# 8-Bit_Selector_2-to-1.net
KiCad netlist of a schematic drawn in EAGLE
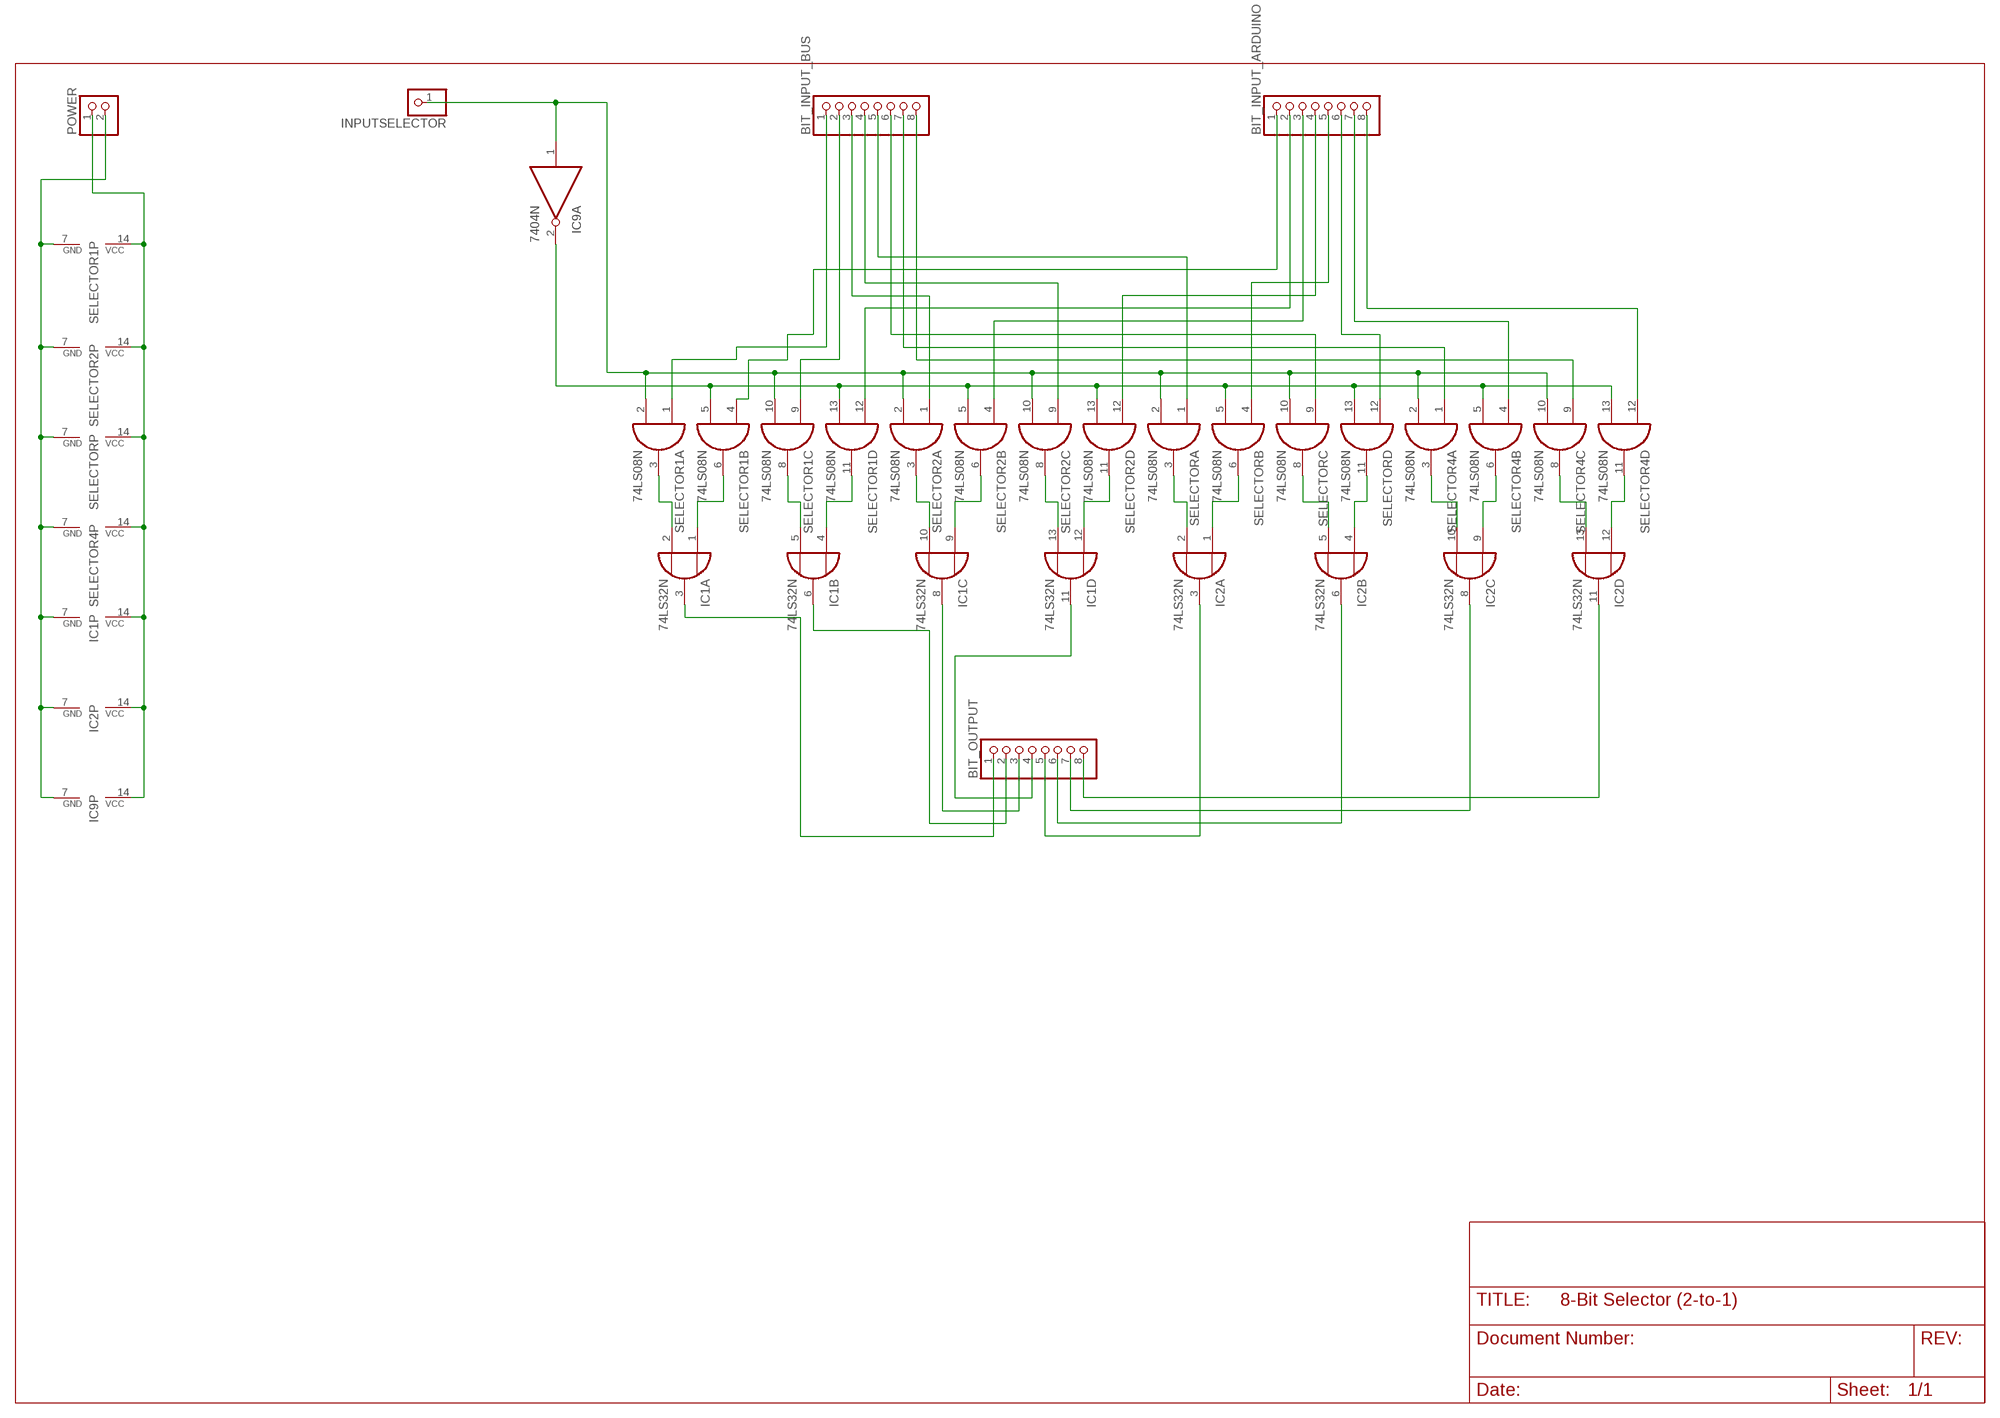
[diagram p0: schematic, sheet 1]

(export (version "E")
  (design (tool "Eeschema 10.0.6"))
  (components
    (comp (ref "BIT_INPUT_ARDUINO")
      (value "PINHD-1X8")
      (footprint "eagle-import:1X08")
      (libsource (lib "eagle-import") (part "PINHD-1X8"))
    )
    (comp (ref "BIT_INPUT_BUS")
      (value "PINHD-1X8")
      (footprint "eagle-import:1X08")
      (libsource (lib "eagle-import") (part "PINHD-1X8"))
    )
    (comp (ref "BIT_OUTPUT")
      (value "PINHD-1X8")
      (footprint "eagle-import:1X08")
      (libsource (lib "eagle-import") (part "PINHD-1X8"))
    )
    (comp (ref "IC1")
      (value "74LS32N")
      (footprint "eagle-import:DIL14")
      (libsource (lib "eagle-import") (part "7432NLS"))
    )
    (comp (ref "IC2")
      (value "74LS32N")
      (footprint "eagle-import:DIL14")
      (libsource (lib "eagle-import") (part "7432NLS"))
    )
    (comp (ref "IC9")
      (value "7404N")
      (footprint "eagle-import:DIL14")
      (libsource (lib "eagle-import") (part "7404N"))
    )
    (comp (ref "INPUTSELECTOR")
      (value "PINHD-1X1")
      (footprint "eagle-import:1X01")
      (libsource (lib "eagle-import") (part "PINHD-1X1"))
    )
    (comp (ref "POWER")
      (value "PINHD-1X2")
      (footprint "eagle-import:1X02")
      (libsource (lib "eagle-import") (part "PINHD-1X2"))
    )
    (comp (ref "SELECTOR")
      (value "74LS08N")
      (footprint "eagle-import:DIL14")
      (libsource (lib "eagle-import") (part "7408NLS"))
    )
    (comp (ref "SELECTOR1")
      (value "74LS08N")
      (footprint "eagle-import:DIL14")
      (libsource (lib "eagle-import") (part "7408NLS"))
    )
    (comp (ref "SELECTOR2")
      (value "74LS08N")
      (footprint "eagle-import:DIL14")
      (libsource (lib "eagle-import") (part "7408NLS"))
    )
    (comp (ref "SELECTOR4")
      (value "74LS08N")
      (footprint "eagle-import:DIL14")
      (libsource (lib "eagle-import") (part "7408NLS"))
    )
  )
  (nets
    (net (code "1") (name "Net-(IC1A-I0)") (class "Default")
      (node (ref "IC1") (pin "1") (pinfunction "I0_1") (pintype "input"))
      (node (ref "SELECTOR1") (pin "6") (pinfunction "O_6") (pintype "output"))
    )
    (net (code "2") (name "Net-(IC1A-I1)") (class "Default")
      (node (ref "IC1") (pin "2") (pinfunction "I1_2") (pintype "input"))
      (node (ref "SELECTOR1") (pin "3") (pinfunction "O_3") (pintype "output"))
    )
    (net (code "3") (name "Net-(IC1A-O)") (class "Default")
      (node (ref "BIT_OUTPUT") (pin "1") (pinfunction "1_1") (pintype "passive"))
      (node (ref "IC1") (pin "3") (pinfunction "O_3") (pintype "output"))
    )
    (net (code "4") (name "Net-(IC1B-I0)") (class "Default")
      (node (ref "IC1") (pin "4") (pinfunction "I0_4") (pintype "input"))
      (node (ref "SELECTOR1") (pin "11") (pinfunction "O_11") (pintype "output"))
    )
    (net (code "5") (name "Net-(IC1B-I1)") (class "Default")
      (node (ref "IC1") (pin "5") (pinfunction "I1_5") (pintype "input"))
      (node (ref "SELECTOR1") (pin "8") (pinfunction "O_8") (pintype "output"))
    )
    (net (code "6") (name "Net-(IC1B-O)") (class "Default")
      (node (ref "BIT_OUTPUT") (pin "2") (pinfunction "2_2") (pintype "passive"))
      (node (ref "IC1") (pin "6") (pinfunction "O_6") (pintype "output"))
    )
    (net (code "7") (name "Net-(IC1C-I0)") (class "Default")
      (node (ref "IC1") (pin "9") (pinfunction "I0_9") (pintype "input"))
      (node (ref "SELECTOR2") (pin "6") (pinfunction "O_6") (pintype "output"))
    )
    (net (code "8") (name "Net-(IC1C-I1)") (class "Default")
      (node (ref "IC1") (pin "10") (pinfunction "I1_10") (pintype "input"))
      (node (ref "SELECTOR2") (pin "3") (pinfunction "O_3") (pintype "output"))
    )
    (net (code "9") (name "Net-(IC1C-O)") (class "Default")
      (node (ref "BIT_OUTPUT") (pin "3") (pinfunction "3_3") (pintype "passive"))
      (node (ref "IC1") (pin "8") (pinfunction "O_8") (pintype "output"))
    )
    (net (code "10") (name "Net-(IC1D-I0)") (class "Default")
      (node (ref "IC1") (pin "12") (pinfunction "I0_12") (pintype "input"))
      (node (ref "SELECTOR2") (pin "11") (pinfunction "O_11") (pintype "output"))
    )
    (net (code "11") (name "Net-(IC1D-I1)") (class "Default")
      (node (ref "IC1") (pin "13") (pinfunction "I1_13") (pintype "input"))
      (node (ref "SELECTOR2") (pin "8") (pinfunction "O_8") (pintype "output"))
    )
    (net (code "12") (name "Net-(IC1D-O)") (class "Default")
      (node (ref "BIT_OUTPUT") (pin "4") (pinfunction "4_4") (pintype "passive"))
      (node (ref "IC1") (pin "11") (pinfunction "O_11") (pintype "output"))
    )
    (net (code "13") (name "Net-(IC1E-GND)") (class "Default")
      (node (ref "IC1") (pin "7") (pinfunction "GND_7") (pintype "power_in"))
      (node (ref "IC2") (pin "7") (pinfunction "GND_7") (pintype "power_in"))
      (node (ref "IC9") (pin "7") (pinfunction "GND_7") (pintype "power_in"))
      (node (ref "POWER") (pin "2") (pinfunction "2_2") (pintype "passive"))
      (node (ref "SELECTOR") (pin "7") (pinfunction "GND_7") (pintype "power_in"))
      (node (ref "SELECTOR1") (pin "7") (pinfunction "GND_7") (pintype "power_in"))
      (node (ref "SELECTOR2") (pin "7") (pinfunction "GND_7") (pintype "power_in"))
      (node (ref "SELECTOR4") (pin "7") (pinfunction "GND_7") (pintype "power_in"))
    )
    (net (code "14") (name "Net-(IC1E-VCC)") (class "Default")
      (node (ref "IC1") (pin "14") (pinfunction "VCC_14") (pintype "power_in"))
      (node (ref "IC2") (pin "14") (pinfunction "VCC_14") (pintype "power_in"))
      (node (ref "IC9") (pin "14") (pinfunction "VCC_14") (pintype "power_in"))
      (node (ref "POWER") (pin "1") (pinfunction "1_1") (pintype "passive"))
      (node (ref "SELECTOR") (pin "14") (pinfunction "VCC_14") (pintype "power_in"))
      (node (ref "SELECTOR1") (pin "14") (pinfunction "VCC_14") (pintype "power_in"))
      (node (ref "SELECTOR2") (pin "14") (pinfunction "VCC_14") (pintype "power_in"))
      (node (ref "SELECTOR4") (pin "14") (pinfunction "VCC_14") (pintype "power_in"))
    )
    (net (code "15") (name "Net-(IC2A-I0)") (class "Default")
      (node (ref "IC2") (pin "1") (pinfunction "I0_1") (pintype "input"))
      (node (ref "SELECTOR") (pin "6") (pinfunction "O_6") (pintype "output"))
    )
    (net (code "16") (name "Net-(IC2A-I1)") (class "Default")
      (node (ref "IC2") (pin "2") (pinfunction "I1_2") (pintype "input"))
      (node (ref "SELECTOR") (pin "3") (pinfunction "O_3") (pintype "output"))
    )
    (net (code "17") (name "Net-(IC2A-O)") (class "Default")
      (node (ref "BIT_OUTPUT") (pin "5") (pinfunction "5_5") (pintype "passive"))
      (node (ref "IC2") (pin "3") (pinfunction "O_3") (pintype "output"))
    )
    (net (code "18") (name "Net-(IC2B-I0)") (class "Default")
      (node (ref "IC2") (pin "4") (pinfunction "I0_4") (pintype "input"))
      (node (ref "SELECTOR") (pin "11") (pinfunction "O_11") (pintype "output"))
    )
    (net (code "19") (name "Net-(IC2B-I1)") (class "Default")
      (node (ref "IC2") (pin "5") (pinfunction "I1_5") (pintype "input"))
      (node (ref "SELECTOR") (pin "8") (pinfunction "O_8") (pintype "output"))
    )
    (net (code "20") (name "Net-(IC2B-O)") (class "Default")
      (node (ref "BIT_OUTPUT") (pin "6") (pinfunction "6_6") (pintype "passive"))
      (node (ref "IC2") (pin "6") (pinfunction "O_6") (pintype "output"))
    )
    (net (code "21") (name "Net-(IC2C-I0)") (class "Default")
      (node (ref "IC2") (pin "9") (pinfunction "I0_9") (pintype "input"))
      (node (ref "SELECTOR4") (pin "6") (pinfunction "O_6") (pintype "output"))
    )
    (net (code "22") (name "Net-(IC2C-I1)") (class "Default")
      (node (ref "IC2") (pin "10") (pinfunction "I1_10") (pintype "input"))
      (node (ref "SELECTOR4") (pin "3") (pinfunction "O_3") (pintype "output"))
    )
    (net (code "23") (name "Net-(IC2C-O)") (class "Default")
      (node (ref "BIT_OUTPUT") (pin "7") (pinfunction "7_7") (pintype "passive"))
      (node (ref "IC2") (pin "8") (pinfunction "O_8") (pintype "output"))
    )
    (net (code "24") (name "Net-(IC2D-I0)") (class "Default")
      (node (ref "IC2") (pin "12") (pinfunction "I0_12") (pintype "input"))
      (node (ref "SELECTOR4") (pin "11") (pinfunction "O_11") (pintype "output"))
    )
    (net (code "25") (name "Net-(IC2D-I1)") (class "Default")
      (node (ref "IC2") (pin "13") (pinfunction "I1_13") (pintype "input"))
      (node (ref "SELECTOR4") (pin "8") (pinfunction "O_8") (pintype "output"))
    )
    (net (code "26") (name "Net-(IC2D-O)") (class "Default")
      (node (ref "BIT_OUTPUT") (pin "8") (pinfunction "8_8") (pintype "passive"))
      (node (ref "IC2") (pin "11") (pinfunction "O_11") (pintype "output"))
    )
    (net (code "27") (name "Net-(IC9A-I)") (class "Default")
      (node (ref "IC9") (pin "1") (pinfunction "I_1") (pintype "input"))
      (node (ref "INPUTSELECTOR") (pin "1") (pinfunction "1_1") (pintype "passive"))
      (node (ref "SELECTOR") (pin "10") (pinfunction "I1_10") (pintype "input"))
      (node (ref "SELECTOR") (pin "2") (pinfunction "I1_2") (pintype "input"))
      (node (ref "SELECTOR1") (pin "10") (pinfunction "I1_10") (pintype "input"))
      (node (ref "SELECTOR1") (pin "2") (pinfunction "I1_2") (pintype "input"))
      (node (ref "SELECTOR2") (pin "10") (pinfunction "I1_10") (pintype "input"))
      (node (ref "SELECTOR2") (pin "2") (pinfunction "I1_2") (pintype "input"))
      (node (ref "SELECTOR4") (pin "10") (pinfunction "I1_10") (pintype "input"))
      (node (ref "SELECTOR4") (pin "2") (pinfunction "I1_2") (pintype "input"))
    )
    (net (code "28") (name "Net-(IC9A-O)") (class "Default")
      (node (ref "IC9") (pin "2") (pinfunction "O_2") (pintype "output"))
      (node (ref "SELECTOR") (pin "13") (pinfunction "I1_13") (pintype "input"))
      (node (ref "SELECTOR") (pin "5") (pinfunction "I1_5") (pintype "input"))
      (node (ref "SELECTOR1") (pin "13") (pinfunction "I1_13") (pintype "input"))
      (node (ref "SELECTOR1") (pin "5") (pinfunction "I1_5") (pintype "input"))
      (node (ref "SELECTOR2") (pin "13") (pinfunction "I1_13") (pintype "input"))
      (node (ref "SELECTOR2") (pin "5") (pinfunction "I1_5") (pintype "input"))
      (node (ref "SELECTOR4") (pin "13") (pinfunction "I1_13") (pintype "input"))
      (node (ref "SELECTOR4") (pin "5") (pinfunction "I1_5") (pintype "input"))
    )
    (net (code "29") (name "Net-(SELECTOR1A-I0)") (class "Default")
      (node (ref "BIT_INPUT_BUS") (pin "1") (pinfunction "1_1") (pintype "passive"))
      (node (ref "SELECTOR1") (pin "1") (pinfunction "I0_1") (pintype "input"))
    )
    (net (code "30") (name "Net-(SELECTOR1B-I0)") (class "Default")
      (node (ref "BIT_INPUT_ARDUINO") (pin "1") (pinfunction "1_1") (pintype "passive"))
      (node (ref "SELECTOR1") (pin "4") (pinfunction "I0_4") (pintype "input"))
    )
    (net (code "31") (name "Net-(SELECTOR1C-I0)") (class "Default")
      (node (ref "BIT_INPUT_BUS") (pin "2") (pinfunction "2_2") (pintype "passive"))
      (node (ref "SELECTOR1") (pin "9") (pinfunction "I0_9") (pintype "input"))
    )
    (net (code "32") (name "Net-(SELECTOR1D-I0)") (class "Default")
      (node (ref "BIT_INPUT_ARDUINO") (pin "2") (pinfunction "2_2") (pintype "passive"))
      (node (ref "SELECTOR1") (pin "12") (pinfunction "I0_12") (pintype "input"))
    )
    (net (code "33") (name "Net-(SELECTOR2A-I0)") (class "Default")
      (node (ref "BIT_INPUT_BUS") (pin "3") (pinfunction "3_3") (pintype "passive"))
      (node (ref "SELECTOR2") (pin "1") (pinfunction "I0_1") (pintype "input"))
    )
    (net (code "34") (name "Net-(SELECTOR2B-I0)") (class "Default")
      (node (ref "BIT_INPUT_ARDUINO") (pin "3") (pinfunction "3_3") (pintype "passive"))
      (node (ref "SELECTOR2") (pin "4") (pinfunction "I0_4") (pintype "input"))
    )
    (net (code "35") (name "Net-(SELECTOR2C-I0)") (class "Default")
      (node (ref "BIT_INPUT_BUS") (pin "4") (pinfunction "4_4") (pintype "passive"))
      (node (ref "SELECTOR2") (pin "9") (pinfunction "I0_9") (pintype "input"))
    )
    (net (code "36") (name "Net-(SELECTOR2D-I0)") (class "Default")
      (node (ref "BIT_INPUT_ARDUINO") (pin "4") (pinfunction "4_4") (pintype "passive"))
      (node (ref "SELECTOR2") (pin "12") (pinfunction "I0_12") (pintype "input"))
    )
    (net (code "37") (name "Net-(SELECTOR4A-I0)") (class "Default")
      (node (ref "BIT_INPUT_BUS") (pin "7") (pinfunction "7_7") (pintype "passive"))
      (node (ref "SELECTOR4") (pin "1") (pinfunction "I0_1") (pintype "input"))
    )
    (net (code "38") (name "Net-(SELECTOR4B-I0)") (class "Default")
      (node (ref "BIT_INPUT_ARDUINO") (pin "7") (pinfunction "7_7") (pintype "passive"))
      (node (ref "SELECTOR4") (pin "4") (pinfunction "I0_4") (pintype "input"))
    )
    (net (code "39") (name "Net-(SELECTOR4C-I0)") (class "Default")
      (node (ref "BIT_INPUT_BUS") (pin "8") (pinfunction "8_8") (pintype "passive"))
      (node (ref "SELECTOR4") (pin "9") (pinfunction "I0_9") (pintype "input"))
    )
    (net (code "40") (name "Net-(SELECTOR4D-I0)") (class "Default")
      (node (ref "BIT_INPUT_ARDUINO") (pin "8") (pinfunction "8_8") (pintype "passive"))
      (node (ref "SELECTOR4") (pin "12") (pinfunction "I0_12") (pintype "input"))
    )
    (net (code "41") (name "Net-(SELECTORA-I0)") (class "Default")
      (node (ref "BIT_INPUT_BUS") (pin "5") (pinfunction "5_5") (pintype "passive"))
      (node (ref "SELECTOR") (pin "1") (pinfunction "I0_1") (pintype "input"))
    )
    (net (code "42") (name "Net-(SELECTORB-I0)") (class "Default")
      (node (ref "BIT_INPUT_ARDUINO") (pin "5") (pinfunction "5_5") (pintype "passive"))
      (node (ref "SELECTOR") (pin "4") (pinfunction "I0_4") (pintype "input"))
    )
    (net (code "43") (name "Net-(SELECTORC-I0)") (class "Default")
      (node (ref "BIT_INPUT_BUS") (pin "6") (pinfunction "6_6") (pintype "passive"))
      (node (ref "SELECTOR") (pin "9") (pinfunction "I0_9") (pintype "input"))
    )
    (net (code "44") (name "Net-(SELECTORD-I0)") (class "Default")
      (node (ref "BIT_INPUT_ARDUINO") (pin "6") (pinfunction "6_6") (pintype "passive"))
      (node (ref "SELECTOR") (pin "12") (pinfunction "I0_12") (pintype "input"))
    )
  )
)
